# Sheet1.net
KiCad netlist of a schematic drawn in Altium Designer
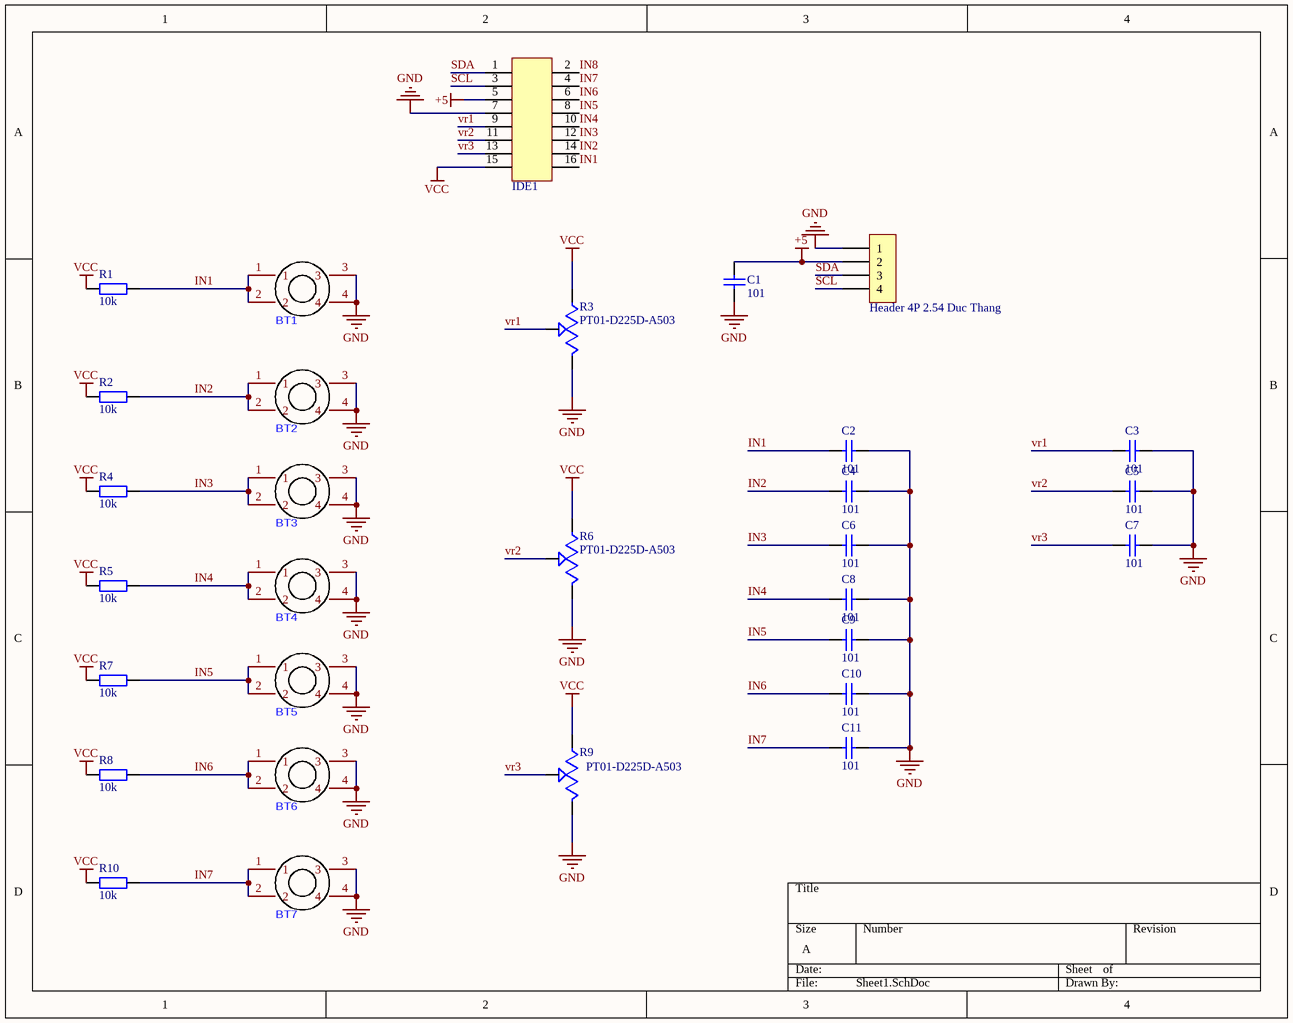
[diagram p0: Sheet1.SchDoc]

(export (version "E")
  (design (tool "Eeschema 10.0.6"))
  (components
    (comp (ref "BT1")
      (value "Nut Nhan 4 chan 12x12")
      (footprint "12X12 BUTTOM Blue")
      (libsource (lib "Altium_Lib_by_KhueNguyenCreator") (part "Nut Nhan 4 chan 12x12"))
    )
    (comp (ref "BT2")
      (value "Nut Nhan 4 chan 12x12")
      (footprint "12X12 BUTTOM Blue")
      (libsource (lib "Altium_Lib_by_KhueNguyenCreator") (part "Nut Nhan 4 chan 12x12"))
    )
    (comp (ref "BT3")
      (value "Nut Nhan 4 chan 12x12")
      (footprint "12X12 BUTTOM Blue")
      (libsource (lib "Altium_Lib_by_KhueNguyenCreator") (part "Nut Nhan 4 chan 12x12"))
    )
    (comp (ref "BT4")
      (value "Nut Nhan 4 chan 12x12")
      (footprint "12X12 BUTTOM Blue")
      (libsource (lib "Altium_Lib_by_KhueNguyenCreator") (part "Nut Nhan 4 chan 12x12"))
    )
    (comp (ref "BT5")
      (value "Nut Nhan 4 chan 12x12")
      (footprint "12X12 BUTTOM Blue")
      (libsource (lib "Altium_Lib_by_KhueNguyenCreator") (part "Nut Nhan 4 chan 12x12"))
    )
    (comp (ref "BT6")
      (value "Nut Nhan 4 chan 12x12")
      (footprint "12X12 BUTTOM Blue")
      (libsource (lib "Altium_Lib_by_KhueNguyenCreator") (part "Nut Nhan 4 chan 12x12"))
    )
    (comp (ref "BT7")
      (value "Nut Nhan 4 chan 12x12")
      (footprint "12X12 BUTTOM Blue")
      (libsource (lib "Altium_Lib_by_KhueNguyenCreator") (part "Nut Nhan 4 chan 12x12"))
    )
    (comp (ref "C1")
      (value "101")
      (footprint "tu 0603")
      (description "Dán")
      (libsource (lib "Altium_Lib_by_KhueNguyenCreator") (part "Tu 0603 104 50V 10%"))
    )
    (comp (ref "C2")
      (value "101")
      (footprint "tu 0603")
      (description "Dán")
      (libsource (lib "Altium_Lib_by_KhueNguyenCreator") (part "Tu 0603 104 50V 10%"))
    )
    (comp (ref "C3")
      (value "101")
      (footprint "tu 0603")
      (description "Dán")
      (libsource (lib "Altium_Lib_by_KhueNguyenCreator") (part "Tu 0603 104 50V 10%"))
    )
    (comp (ref "C4")
      (value "101")
      (footprint "tu 0603")
      (description "Dán")
      (libsource (lib "Altium_Lib_by_KhueNguyenCreator") (part "Tu 0603 104 50V 10%"))
    )
    (comp (ref "C5")
      (value "101")
      (footprint "tu 0603")
      (description "Dán")
      (libsource (lib "Altium_Lib_by_KhueNguyenCreator") (part "Tu 0603 104 50V 10%"))
    )
    (comp (ref "C6")
      (value "101")
      (footprint "tu 0603")
      (description "Dán")
      (libsource (lib "Altium_Lib_by_KhueNguyenCreator") (part "Tu 0603 104 50V 10%"))
    )
    (comp (ref "C7")
      (value "101")
      (footprint "tu 0603")
      (description "Dán")
      (libsource (lib "Altium_Lib_by_KhueNguyenCreator") (part "Tu 0603 104 50V 10%"))
    )
    (comp (ref "C8")
      (value "101")
      (footprint "tu 0603")
      (description "Dán")
      (libsource (lib "Altium_Lib_by_KhueNguyenCreator") (part "Tu 0603 104 50V 10%"))
    )
    (comp (ref "C9")
      (value "101")
      (footprint "tu 0603")
      (description "Dán")
      (libsource (lib "Altium_Lib_by_KhueNguyenCreator") (part "Tu 0603 104 50V 10%"))
    )
    (comp (ref "C10")
      (value "101")
      (footprint "tu 0603")
      (description "Dán")
      (libsource (lib "Altium_Lib_by_KhueNguyenCreator") (part "Tu 0603 104 50V 10%"))
    )
    (comp (ref "C11")
      (value "101")
      (footprint "tu 0603")
      (description "Dán")
      (libsource (lib "Altium_Lib_by_KhueNguyenCreator") (part "Tu 0603 104 50V 10%"))
    )
    (comp (ref "IDE1")
      (value "IDE16")
      (footprint "IDE16 DT")
      (libsource (lib "Altium_Lib_by_KhueNguyenCreator") (part "IDE 16 DT"))
    )
    (comp (ref "LCD")
      (value "Header 4P 2.54 Duc Thang")
      (footprint "XH2.54M-4")
      (description "Cắm")
      (libsource (lib "Altium_Lib_by_KhueNguyenCreator") (part "Header 4P 2.54 Duc Thang"))
    )
    (comp (ref "R1")
      (value "10k")
      (footprint "tro smd 0603")
      (description "Dán")
      (libsource (lib "Altium_Lib_by_KhueNguyenCreator") (part "Tro 0603 5% 10k"))
    )
    (comp (ref "R2")
      (value "10k")
      (footprint "tro smd 0603")
      (description "Dán")
      (libsource (lib "Altium_Lib_by_KhueNguyenCreator") (part "Tro 0603 5% 10k"))
    )
    (comp (ref "R3")
      (value "PT01-D225D-A503")
      (footprint "TRIM_PT01-D225D-A503")
      (description "10 mm, Vertical, Logarithmic, 50 kÎ©, Through Hole, D-cut Rotary Potentiometer")
      (fields (field (name "MF") "Same Sky"))
      (libsource (lib "PT01-D225D-A503_fixed") (part "PT01-D225D-A503"))
    )
    (comp (ref "R4")
      (value "10k")
      (footprint "tro smd 0603")
      (description "Dán")
      (libsource (lib "Altium_Lib_by_KhueNguyenCreator") (part "Tro 0603 5% 10k"))
    )
    (comp (ref "R5")
      (value "10k")
      (footprint "tro smd 0603")
      (description "Dán")
      (libsource (lib "Altium_Lib_by_KhueNguyenCreator") (part "Tro 0603 5% 10k"))
    )
    (comp (ref "R6")
      (value "PT01-D225D-A503")
      (footprint "TRIM_PT01-D225D-A503")
      (description "10 mm, Vertical, Logarithmic, 50 kÎ©, Through Hole, D-cut Rotary Potentiometer")
      (fields (field (name "MF") "Same Sky"))
      (libsource (lib "PT01-D225D-A503_fixed") (part "PT01-D225D-A503"))
    )
    (comp (ref "R7")
      (value "10k")
      (footprint "tro smd 0603")
      (description "Dán")
      (libsource (lib "Altium_Lib_by_KhueNguyenCreator") (part "Tro 0603 5% 10k"))
    )
    (comp (ref "R8")
      (value "10k")
      (footprint "tro smd 0603")
      (description "Dán")
      (libsource (lib "Altium_Lib_by_KhueNguyenCreator") (part "Tro 0603 5% 10k"))
    )
    (comp (ref "R9")
      (value "PT01-D225D-A503")
      (footprint "TRIM_PT01-D225D-A503")
      (description "10 mm, Vertical, Logarithmic, 50 kÎ©, Through Hole, D-cut Rotary Potentiometer")
      (fields (field (name "MF") "Same Sky"))
      (libsource (lib "PT01-D225D-A503_fixed") (part "PT01-D225D-A503"))
    )
    (comp (ref "R10")
      (value "10k")
      (footprint "tro smd 0603")
      (description "Dán")
      (libsource (lib "Altium_Lib_by_KhueNguyenCreator") (part "Tro 0603 5% 10k"))
    )
  )
  (nets
    (net (code "1") (name "+5") (class "Default")
      (node (ref "C1") (pin "1") (pinfunction "1_1") (pintype "passive"))
      (node (ref "IDE1") (pin "5") (pinfunction "5_5") (pintype "passive"))
      (node (ref "LCD") (pin "2") (pinfunction "2_2") (pintype "passive"))
    )
    (net (code "2") (name "/IN1") (class "Default")
      (node (ref "BT1") (pin "1") (pinfunction "1_1") (pintype "passive"))
      (node (ref "BT1") (pin "2") (pinfunction "2_2") (pintype "passive"))
      (node (ref "C2") (pin "2") (pinfunction "2_2") (pintype "passive"))
      (node (ref "IDE1") (pin "16") (pinfunction "14_16") (pintype "passive"))
      (node (ref "R1") (pin "2") (pinfunction "2_2") (pintype "passive"))
    )
    (net (code "3") (name "/IN2") (class "Default")
      (node (ref "BT2") (pin "1") (pinfunction "1_1") (pintype "passive"))
      (node (ref "BT2") (pin "2") (pinfunction "2_2") (pintype "passive"))
      (node (ref "C4") (pin "2") (pinfunction "2_2") (pintype "passive"))
      (node (ref "IDE1") (pin "14") (pinfunction "14_14") (pintype "passive"))
      (node (ref "R2") (pin "2") (pinfunction "2_2") (pintype "passive"))
    )
    (net (code "4") (name "/IN3") (class "Default")
      (node (ref "BT3") (pin "1") (pinfunction "1_1") (pintype "passive"))
      (node (ref "BT3") (pin "2") (pinfunction "2_2") (pintype "passive"))
      (node (ref "C6") (pin "2") (pinfunction "2_2") (pintype "passive"))
      (node (ref "IDE1") (pin "12") (pinfunction "12_12") (pintype "passive"))
      (node (ref "R4") (pin "2") (pinfunction "2_2") (pintype "passive"))
    )
    (net (code "5") (name "/IN4") (class "Default")
      (node (ref "BT4") (pin "1") (pinfunction "1_1") (pintype "passive"))
      (node (ref "BT4") (pin "2") (pinfunction "2_2") (pintype "passive"))
      (node (ref "C8") (pin "2") (pinfunction "2_2") (pintype "passive"))
      (node (ref "IDE1") (pin "10") (pinfunction "10_10") (pintype "passive"))
      (node (ref "R5") (pin "2") (pinfunction "2_2") (pintype "passive"))
    )
    (net (code "6") (name "/IN5") (class "Default")
      (node (ref "BT5") (pin "1") (pinfunction "1_1") (pintype "passive"))
      (node (ref "BT5") (pin "2") (pinfunction "2_2") (pintype "passive"))
      (node (ref "C9") (pin "2") (pinfunction "2_2") (pintype "passive"))
      (node (ref "IDE1") (pin "8") (pinfunction "8_8") (pintype "passive"))
      (node (ref "R7") (pin "2") (pinfunction "2_2") (pintype "passive"))
    )
    (net (code "7") (name "/IN6") (class "Default")
      (node (ref "BT6") (pin "1") (pinfunction "1_1") (pintype "passive"))
      (node (ref "BT6") (pin "2") (pinfunction "2_2") (pintype "passive"))
      (node (ref "C10") (pin "2") (pinfunction "2_2") (pintype "passive"))
      (node (ref "IDE1") (pin "6") (pinfunction "6_6") (pintype "passive"))
      (node (ref "R8") (pin "2") (pinfunction "2_2") (pintype "passive"))
    )
    (net (code "8") (name "/IN7") (class "Default")
      (node (ref "BT7") (pin "1") (pinfunction "1_1") (pintype "passive"))
      (node (ref "BT7") (pin "2") (pinfunction "2_2") (pintype "passive"))
      (node (ref "C11") (pin "2") (pinfunction "2_2") (pintype "passive"))
      (node (ref "IDE1") (pin "4") (pinfunction "4_4") (pintype "passive"))
      (node (ref "R10") (pin "2") (pinfunction "2_2") (pintype "passive"))
    )
    (net (code "9") (name "/IN8") (class "Default")
      (node (ref "IDE1") (pin "2") (pinfunction "2_2") (pintype "passive"))
    )
    (net (code "10") (name "/SCL") (class "Default")
      (node (ref "IDE1") (pin "3") (pinfunction "3_3") (pintype "passive"))
      (node (ref "LCD") (pin "4") (pinfunction "4_4") (pintype "passive"))
    )
    (net (code "11") (name "/SDA") (class "Default")
      (node (ref "IDE1") (pin "1") (pinfunction "1_1") (pintype "passive"))
      (node (ref "LCD") (pin "3") (pinfunction "3_3") (pintype "passive"))
    )
    (net (code "12") (name "/vr1") (class "Default")
      (node (ref "C3") (pin "2") (pinfunction "2_2") (pintype "passive"))
      (node (ref "IDE1") (pin "9") (pinfunction "9_9") (pintype "passive"))
      (node (ref "R3") (pin "2") (pinfunction "2_2") (pintype "passive"))
    )
    (net (code "13") (name "/vr2") (class "Default")
      (node (ref "C5") (pin "2") (pinfunction "2_2") (pintype "passive"))
      (node (ref "IDE1") (pin "11") (pinfunction "11_11") (pintype "passive"))
      (node (ref "R6") (pin "2") (pinfunction "2_2") (pintype "passive"))
    )
    (net (code "14") (name "/vr3") (class "Default")
      (node (ref "C7") (pin "2") (pinfunction "2_2") (pintype "passive"))
      (node (ref "IDE1") (pin "13") (pinfunction "13_13") (pintype "passive"))
      (node (ref "R9") (pin "2") (pinfunction "2_2") (pintype "passive"))
    )
    (net (code "15") (name "GND") (class "Default")
      (node (ref "BT1") (pin "3") (pinfunction "3_3") (pintype "passive"))
      (node (ref "BT1") (pin "4") (pinfunction "4_4") (pintype "passive"))
      (node (ref "BT2") (pin "3") (pinfunction "3_3") (pintype "passive"))
      (node (ref "BT2") (pin "4") (pinfunction "4_4") (pintype "passive"))
      (node (ref "BT3") (pin "3") (pinfunction "3_3") (pintype "passive"))
      (node (ref "BT3") (pin "4") (pinfunction "4_4") (pintype "passive"))
      (node (ref "BT4") (pin "3") (pinfunction "3_3") (pintype "passive"))
      (node (ref "BT4") (pin "4") (pinfunction "4_4") (pintype "passive"))
      (node (ref "BT5") (pin "3") (pinfunction "3_3") (pintype "passive"))
      (node (ref "BT5") (pin "4") (pinfunction "4_4") (pintype "passive"))
      (node (ref "BT6") (pin "3") (pinfunction "3_3") (pintype "passive"))
      (node (ref "BT6") (pin "4") (pinfunction "4_4") (pintype "passive"))
      (node (ref "BT7") (pin "3") (pinfunction "3_3") (pintype "passive"))
      (node (ref "BT7") (pin "4") (pinfunction "4_4") (pintype "passive"))
      (node (ref "C1") (pin "2") (pinfunction "2_2") (pintype "passive"))
      (node (ref "C10") (pin "1") (pinfunction "1_1") (pintype "passive"))
      (node (ref "C11") (pin "1") (pinfunction "1_1") (pintype "passive"))
      (node (ref "C2") (pin "1") (pinfunction "1_1") (pintype "passive"))
      (node (ref "C3") (pin "1") (pinfunction "1_1") (pintype "passive"))
      (node (ref "C4") (pin "1") (pinfunction "1_1") (pintype "passive"))
      (node (ref "C5") (pin "1") (pinfunction "1_1") (pintype "passive"))
      (node (ref "C6") (pin "1") (pinfunction "1_1") (pintype "passive"))
      (node (ref "C7") (pin "1") (pinfunction "1_1") (pintype "passive"))
      (node (ref "C8") (pin "1") (pinfunction "1_1") (pintype "passive"))
      (node (ref "C9") (pin "1") (pinfunction "1_1") (pintype "passive"))
      (node (ref "IDE1") (pin "7") (pinfunction "7_7") (pintype "passive"))
      (node (ref "LCD") (pin "1") (pinfunction "1_1") (pintype "passive"))
      (node (ref "R3") (pin "1") (pinfunction "1_1") (pintype "passive"))
      (node (ref "R6") (pin "1") (pinfunction "1_1") (pintype "passive"))
      (node (ref "R9") (pin "1") (pinfunction "1_1") (pintype "passive"))
    )
    (net (code "16") (name "VCC") (class "Default")
      (node (ref "IDE1") (pin "15") (pinfunction "14_15") (pintype "passive"))
      (node (ref "R1") (pin "1") (pinfunction "1_1") (pintype "passive"))
      (node (ref "R10") (pin "1") (pinfunction "1_1") (pintype "passive"))
      (node (ref "R2") (pin "1") (pinfunction "1_1") (pintype "passive"))
      (node (ref "R3") (pin "3") (pinfunction "3_3") (pintype "passive"))
      (node (ref "R4") (pin "1") (pinfunction "1_1") (pintype "passive"))
      (node (ref "R5") (pin "1") (pinfunction "1_1") (pintype "passive"))
      (node (ref "R6") (pin "3") (pinfunction "3_3") (pintype "passive"))
      (node (ref "R7") (pin "1") (pinfunction "1_1") (pintype "passive"))
      (node (ref "R8") (pin "1") (pinfunction "1_1") (pintype "passive"))
      (node (ref "R9") (pin "3") (pinfunction "3_3") (pintype "passive"))
    )
  )
)
